# Sheet1.net
KiCad netlist of a schematic drawn in Altium Designer
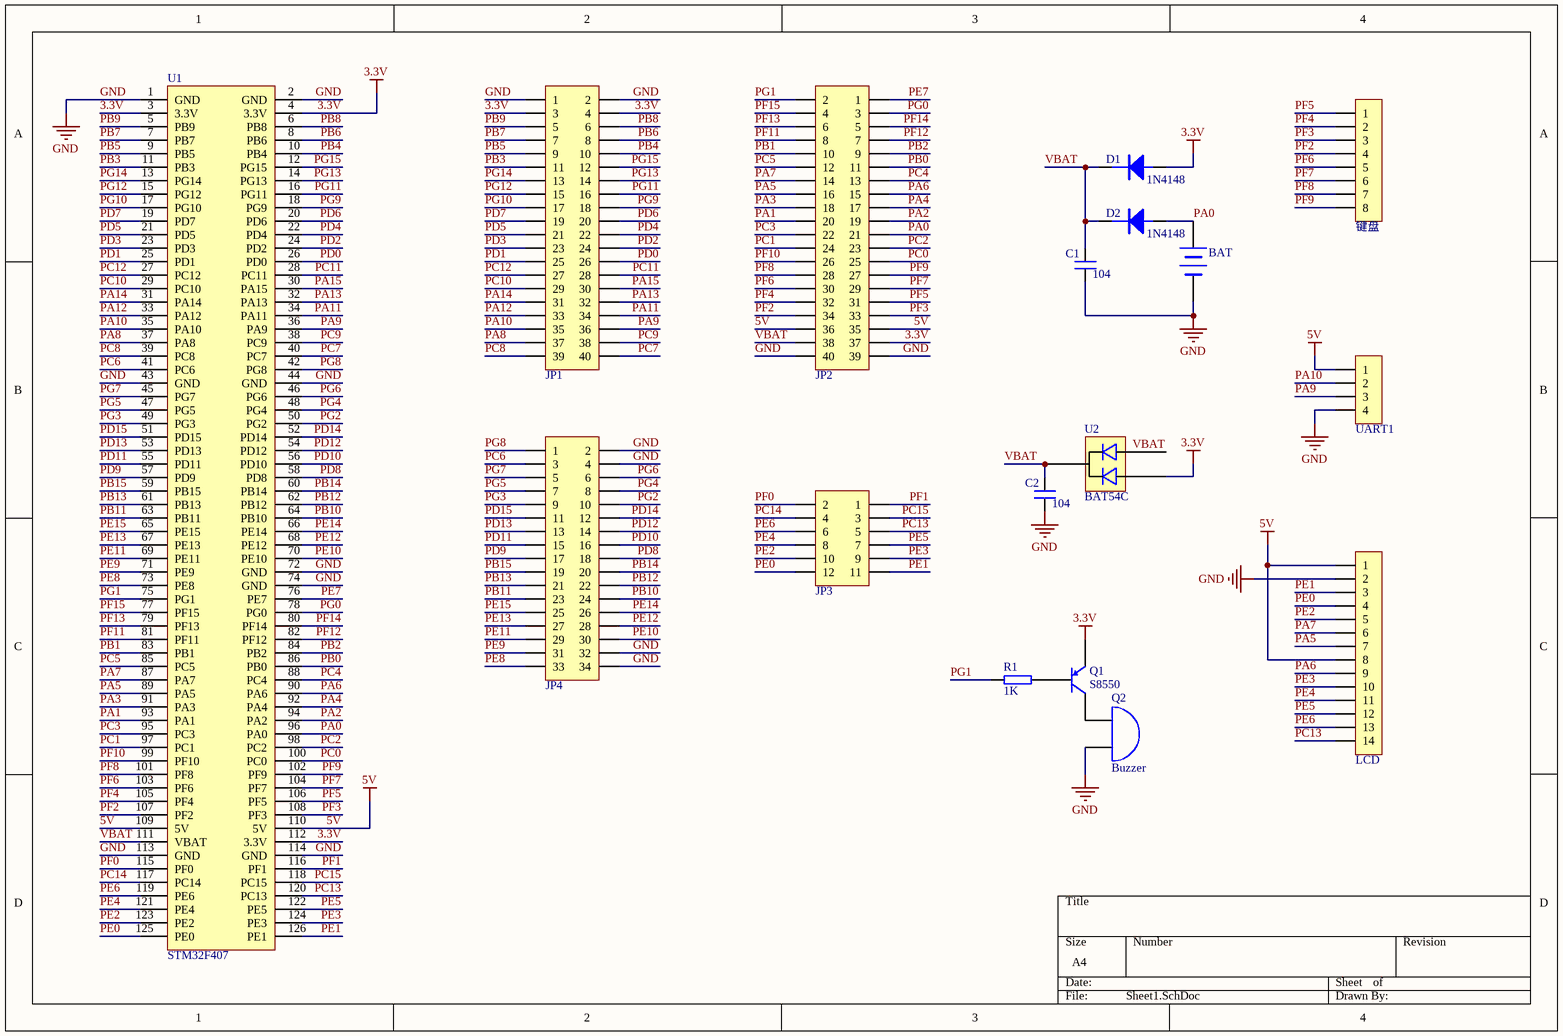
[diagram p0: Sheet1.SchDoc]

(export (version "E")
  (design (tool "Eeschema 10.0.6"))
  (components
    (comp (ref "BAT") (value "~") (footprint "BAT_SMD") (libsource (lib "Schlib1") (part "battery")))
    (comp (ref "C1")
      (value "104")
      (footprint "0805C")
      (description "电容")
      (fields (field (name "版权归属") "源创客"))
      (libsource (lib "Schlib1") (part "Capacitor"))
    )
    (comp (ref "C2")
      (value "104")
      (footprint "0805C")
      (description "电容")
      (fields (field (name "版权归属") "源创客"))
      (libsource (lib "Schlib1") (part "Capacitor"))
    )
    (comp (ref "D1") (value "1N4148") (footprint "SOD-123") (libsource (lib "Schlib1") (part "二极管")))
    (comp (ref "D2") (value "1N4148") (footprint "SOD-123") (libsource (lib "Schlib1") (part "二极管")))
    (comp (ref "JP1")
      (value "Header 2X11")
      (footprint "HDR-20X2")
      (description "20*2P接插件")
      (fields (field (name "版权归属") "源创客"))
      (libsource (lib "Schlib1") (part "Header 20X2u"))
    )
    (comp (ref "JP2")
      (value "Header 2X11")
      (footprint "HDR-20X2")
      (description "20*2P接插件")
      (fields (field (name "版权归属") "源创客"))
      (libsource (lib "") (part "Header 20X2u_1"))
    )
    (comp (ref "JP3")
      (value "Header 6X2")
      (footprint "HDR-6X2")
      (description "6*2P接插件")
      (fields (field (name "版权归属") "源创客"))
      (libsource (lib "Schlib1") (part "Header  6X2u"))
    )
    (comp (ref "JP4")
      (value "Header 2X11")
      (footprint "HDR-17X2")
      (description "17*2P接插件")
      (fields (field (name "版权归属") "源创客"))
      (libsource (lib "Schlib1") (part "Header 17X2u"))
    )
    (comp (ref "LCD")
      (value "HDR-1X14")
      (footprint "HDR-1X14_M")
      (description "14P接插件")
      (fields (field (name "版权归属") "源创客"))
      (libsource (lib "Schlib1") (part "Header 14u"))
    )
    (comp (ref "Q1") (value "S8550") (footprint "BAT54C/S8550") (libsource (lib "Schlib1") (part "S8550")))
    (comp (ref "Q2") (value "Buzzer") (footprint "7525蜂鸣器") (libsource (lib "Schlib1") (part "Buzzer")))
    (comp (ref "R1")
      (value "1K")
      (footprint "0805R")
      (description "电阻")
      (fields (field (name "版权归属") "源创客"))
      (libsource (lib "Schlib1") (part "Resistor"))
    )
    (comp (ref "U1")
      (value "STM32F407")
      (footprint "STM32F407ZGT6")
      (description "Header, 126-Pin, Dual row")
      (fields (field (name "PUBLISHER") "Altium Limited"))
      (libsource (lib "Schlib1") (part "STM32F407"))
    )
    (comp (ref "U2") (value "BAT54C") (footprint "BAT54C") (libsource (lib "Schlib1") (part "BAT54C")))
    (comp (ref "UART1")
      (value "HDR-1X4")
      (footprint "HDR-1X4")
      (description "4P接插件")
      (fields (field (name "版权归属") "源创客"))
      (libsource (lib "Schlib1") (part "Header 4u"))
    )
    (comp (ref "键盘")
      (value "HDR-1X8")
      (footprint "HDR-1X8_M")
      (description "8P接插件")
      (fields (field (name "版权归属") "源创客"))
      (libsource (lib "Schlib1") (part "Header 8u"))
    )
  )
  (nets
    (net (code "1") (name "/PA0") (class "Default")
      (node (ref "BAT") (pin "1") (pinfunction "+_1") (pintype "passive"))
      (node (ref "D2") (pin "1") (pinfunction "A_1") (pintype "passive"))
      (node (ref "JP2") (pin "21") (pinfunction "21_21") (pintype "passive"))
      (node (ref "U1") (pin "96") (pinfunction "PA0_96") (pintype "passive"))
    )
    (net (code "2") (name "/PA1") (class "Default")
      (node (ref "JP2") (pin "20") (pinfunction "20_20") (pintype "passive"))
      (node (ref "U1") (pin "93") (pinfunction "PA1_93") (pintype "passive"))
    )
    (net (code "3") (name "/PA2") (class "Default")
      (node (ref "JP2") (pin "19") (pinfunction "19_19") (pintype "passive"))
      (node (ref "U1") (pin "94") (pinfunction "PA2_94") (pintype "passive"))
    )
    (net (code "4") (name "/PA3") (class "Default")
      (node (ref "JP2") (pin "18") (pinfunction "18_18") (pintype "passive"))
      (node (ref "U1") (pin "91") (pinfunction "PA3_91") (pintype "passive"))
    )
    (net (code "5") (name "/PA4") (class "Default")
      (node (ref "JP2") (pin "17") (pinfunction "17_17") (pintype "passive"))
      (node (ref "U1") (pin "92") (pinfunction "PA4_92") (pintype "passive"))
    )
    (net (code "6") (name "/PA5") (class "Default")
      (node (ref "JP2") (pin "16") (pinfunction "16_16") (pintype "passive"))
      (node (ref "LCD") (pin "7") (pinfunction "7_7") (pintype "passive"))
      (node (ref "U1") (pin "89") (pinfunction "PA5_89") (pintype "passive"))
    )
    (net (code "7") (name "/PA6") (class "Default")
      (node (ref "JP2") (pin "15") (pinfunction "15_15") (pintype "passive"))
      (node (ref "LCD") (pin "9") (pinfunction "9_9") (pintype "passive"))
      (node (ref "U1") (pin "90") (pinfunction "PA6_90") (pintype "passive"))
    )
    (net (code "8") (name "/PA7") (class "Default")
      (node (ref "JP2") (pin "14") (pinfunction "14_14") (pintype "passive"))
      (node (ref "LCD") (pin "6") (pinfunction "6_6") (pintype "passive"))
      (node (ref "U1") (pin "87") (pinfunction "PA7_87") (pintype "passive"))
    )
    (net (code "9") (name "/PA8") (class "Default")
      (node (ref "JP1") (pin "37") (pinfunction "37_37") (pintype "passive"))
      (node (ref "U1") (pin "37") (pinfunction "PA8_37") (pintype "passive"))
    )
    (net (code "10") (name "/PA9") (class "Default")
      (node (ref "JP1") (pin "36") (pinfunction "36_36") (pintype "passive"))
      (node (ref "U1") (pin "36") (pinfunction "PA9_36") (pintype "passive"))
      (node (ref "UART1") (pin "3") (pinfunction "3_3") (pintype "passive"))
    )
    (net (code "11") (name "/PA10") (class "Default")
      (node (ref "JP1") (pin "35") (pinfunction "35_35") (pintype "passive"))
      (node (ref "U1") (pin "35") (pinfunction "PA10_35") (pintype "passive"))
      (node (ref "UART1") (pin "2") (pinfunction "2_2") (pintype "passive"))
    )
    (net (code "12") (name "/PA11") (class "Default")
      (node (ref "JP1") (pin "34") (pinfunction "34_34") (pintype "passive"))
      (node (ref "U1") (pin "34") (pinfunction "PA11_34") (pintype "passive"))
    )
    (net (code "13") (name "/PA12") (class "Default")
      (node (ref "JP1") (pin "33") (pinfunction "33_33") (pintype "passive"))
      (node (ref "U1") (pin "33") (pinfunction "PA12_33") (pintype "passive"))
    )
    (net (code "14") (name "/PA13") (class "Default")
      (node (ref "JP1") (pin "32") (pinfunction "32_32") (pintype "passive"))
      (node (ref "U1") (pin "32") (pinfunction "PA13_32") (pintype "passive"))
    )
    (net (code "15") (name "/PA14") (class "Default")
      (node (ref "JP1") (pin "31") (pinfunction "31_31") (pintype "passive"))
      (node (ref "U1") (pin "31") (pinfunction "PA14_31") (pintype "passive"))
    )
    (net (code "16") (name "/PA15") (class "Default")
      (node (ref "JP1") (pin "30") (pinfunction "30_30") (pintype "passive"))
      (node (ref "U1") (pin "30") (pinfunction "PA15_30") (pintype "passive"))
    )
    (net (code "17") (name "/PB0") (class "Default")
      (node (ref "JP2") (pin "11") (pinfunction "11_11") (pintype "passive"))
      (node (ref "U1") (pin "86") (pinfunction "PB0_86") (pintype "passive"))
    )
    (net (code "18") (name "/PB1") (class "Default")
      (node (ref "JP2") (pin "10") (pinfunction "10_10") (pintype "passive"))
      (node (ref "U1") (pin "83") (pinfunction "PB1_83") (pintype "passive"))
    )
    (net (code "19") (name "/PB2") (class "Default")
      (node (ref "JP2") (pin "9") (pinfunction "9_9") (pintype "passive"))
      (node (ref "U1") (pin "84") (pinfunction "PB2_84") (pintype "passive"))
    )
    (net (code "20") (name "/PB3") (class "Default")
      (node (ref "JP1") (pin "11") (pinfunction "11_11") (pintype "passive"))
      (node (ref "U1") (pin "11") (pinfunction "PB3_11") (pintype "passive"))
    )
    (net (code "21") (name "/PB4") (class "Default")
      (node (ref "JP1") (pin "10") (pinfunction "10_10") (pintype "passive"))
      (node (ref "U1") (pin "10") (pinfunction "PB4_10") (pintype "passive"))
    )
    (net (code "22") (name "/PB5") (class "Default")
      (node (ref "JP1") (pin "9") (pinfunction "9_9") (pintype "passive"))
      (node (ref "U1") (pin "9") (pinfunction "PB5_9") (pintype "passive"))
    )
    (net (code "23") (name "/PB6") (class "Default")
      (node (ref "JP1") (pin "8") (pinfunction "8_8") (pintype "passive"))
      (node (ref "U1") (pin "8") (pinfunction "PB6_8") (pintype "passive"))
    )
    (net (code "24") (name "/PB7") (class "Default")
      (node (ref "JP1") (pin "7") (pinfunction "7_7") (pintype "passive"))
      (node (ref "U1") (pin "7") (pinfunction "PB7_7") (pintype "passive"))
    )
    (net (code "25") (name "/PB8") (class "Default")
      (node (ref "JP1") (pin "6") (pinfunction "6_6") (pintype "passive"))
      (node (ref "U1") (pin "6") (pinfunction "PB8_6") (pintype "passive"))
    )
    (net (code "26") (name "/PB9") (class "Default")
      (node (ref "JP1") (pin "5") (pinfunction "5_5") (pintype "passive"))
      (node (ref "U1") (pin "5") (pinfunction "PB9_5") (pintype "passive"))
    )
    (net (code "27") (name "/PB10") (class "Default")
      (node (ref "JP4") (pin "24") (pinfunction "24_24") (pintype "passive"))
      (node (ref "U1") (pin "64") (pinfunction "PB10_64") (pintype "passive"))
    )
    (net (code "28") (name "/PB11") (class "Default")
      (node (ref "JP4") (pin "23") (pinfunction "23_23") (pintype "passive"))
      (node (ref "U1") (pin "63") (pinfunction "PB11_63") (pintype "passive"))
    )
    (net (code "29") (name "/PB12") (class "Default")
      (node (ref "JP4") (pin "22") (pinfunction "22_22") (pintype "passive"))
      (node (ref "U1") (pin "62") (pinfunction "PB12_62") (pintype "passive"))
    )
    (net (code "30") (name "/PB13") (class "Default")
      (node (ref "JP4") (pin "21") (pinfunction "21_21") (pintype "passive"))
      (node (ref "U1") (pin "61") (pinfunction "PB13_61") (pintype "passive"))
    )
    (net (code "31") (name "/PB14") (class "Default")
      (node (ref "JP4") (pin "20") (pinfunction "20_20") (pintype "passive"))
      (node (ref "U1") (pin "60") (pinfunction "PB14_60") (pintype "passive"))
    )
    (net (code "32") (name "/PB15") (class "Default")
      (node (ref "JP4") (pin "19") (pinfunction "19_19") (pintype "passive"))
      (node (ref "U1") (pin "59") (pinfunction "PB15_59") (pintype "passive"))
    )
    (net (code "33") (name "/PC0") (class "Default")
      (node (ref "JP2") (pin "25") (pinfunction "25_25") (pintype "passive"))
      (node (ref "U1") (pin "100") (pinfunction "PC0_100") (pintype "passive"))
    )
    (net (code "34") (name "/PC1") (class "Default")
      (node (ref "JP2") (pin "24") (pinfunction "24_24") (pintype "passive"))
      (node (ref "U1") (pin "97") (pinfunction "PC1_97") (pintype "passive"))
    )
    (net (code "35") (name "/PC2") (class "Default")
      (node (ref "JP2") (pin "23") (pinfunction "23_23") (pintype "passive"))
      (node (ref "U1") (pin "98") (pinfunction "PC2_98") (pintype "passive"))
    )
    (net (code "36") (name "/PC3") (class "Default")
      (node (ref "JP2") (pin "22") (pinfunction "22_22") (pintype "passive"))
      (node (ref "U1") (pin "95") (pinfunction "PC3_95") (pintype "passive"))
    )
    (net (code "37") (name "/PC4") (class "Default")
      (node (ref "JP2") (pin "13") (pinfunction "13_13") (pintype "passive"))
      (node (ref "U1") (pin "88") (pinfunction "PC4_88") (pintype "passive"))
    )
    (net (code "38") (name "/PC5") (class "Default")
      (node (ref "JP2") (pin "12") (pinfunction "12_12") (pintype "passive"))
      (node (ref "U1") (pin "85") (pinfunction "PC5_85") (pintype "passive"))
    )
    (net (code "39") (name "/PC6") (class "Default")
      (node (ref "JP4") (pin "3") (pinfunction "3_3") (pintype "passive"))
      (node (ref "U1") (pin "41") (pinfunction "PC6_41") (pintype "passive"))
    )
    (net (code "40") (name "/PC7") (class "Default")
      (node (ref "JP1") (pin "40") (pinfunction "40_40") (pintype "passive"))
      (node (ref "U1") (pin "40") (pinfunction "PC7_40") (pintype "passive"))
    )
    (net (code "41") (name "/PC8") (class "Default")
      (node (ref "JP1") (pin "39") (pinfunction "39_39") (pintype "passive"))
      (node (ref "U1") (pin "39") (pinfunction "PC8_39") (pintype "passive"))
    )
    (net (code "42") (name "/PC9") (class "Default")
      (node (ref "JP1") (pin "38") (pinfunction "38_38") (pintype "passive"))
      (node (ref "U1") (pin "38") (pinfunction "PC9_38") (pintype "passive"))
    )
    (net (code "43") (name "/PC10") (class "Default")
      (node (ref "JP1") (pin "29") (pinfunction "29_29") (pintype "passive"))
      (node (ref "U1") (pin "29") (pinfunction "PC10_29") (pintype "passive"))
    )
    (net (code "44") (name "/PC11") (class "Default")
      (node (ref "JP1") (pin "28") (pinfunction "28_28") (pintype "passive"))
      (node (ref "U1") (pin "28") (pinfunction "PC11_28") (pintype "passive"))
    )
    (net (code "45") (name "/PC12") (class "Default")
      (node (ref "JP1") (pin "27") (pinfunction "27_27") (pintype "passive"))
      (node (ref "U1") (pin "27") (pinfunction "PC12_27") (pintype "passive"))
    )
    (net (code "46") (name "/PC13") (class "Default")
      (node (ref "JP3") (pin "5") (pinfunction "5_5") (pintype "passive"))
      (node (ref "LCD") (pin "14") (pinfunction "14_14") (pintype "passive"))
      (node (ref "U1") (pin "120") (pinfunction "PC13_120") (pintype "passive"))
    )
    (net (code "47") (name "/PC14") (class "Default")
      (node (ref "JP3") (pin "4") (pinfunction "4_4") (pintype "passive"))
      (node (ref "U1") (pin "117") (pinfunction "PC14_117") (pintype "passive"))
    )
    (net (code "48") (name "/PC15") (class "Default")
      (node (ref "JP3") (pin "3") (pinfunction "3_3") (pintype "passive"))
      (node (ref "U1") (pin "118") (pinfunction "PC15_118") (pintype "passive"))
    )
    (net (code "49") (name "/PD0") (class "Default")
      (node (ref "JP1") (pin "26") (pinfunction "26_26") (pintype "passive"))
      (node (ref "U1") (pin "26") (pinfunction "PD0_26") (pintype "passive"))
    )
    (net (code "50") (name "/PD1") (class "Default")
      (node (ref "JP1") (pin "25") (pinfunction "25_25") (pintype "passive"))
      (node (ref "U1") (pin "25") (pinfunction "PD1_25") (pintype "passive"))
    )
    (net (code "51") (name "/PD2") (class "Default")
      (node (ref "JP1") (pin "24") (pinfunction "24_24") (pintype "passive"))
      (node (ref "U1") (pin "24") (pinfunction "PD2_24") (pintype "passive"))
    )
    (net (code "52") (name "/PD3") (class "Default")
      (node (ref "JP1") (pin "23") (pinfunction "23_23") (pintype "passive"))
      (node (ref "U1") (pin "23") (pinfunction "PD3_23") (pintype "passive"))
    )
    (net (code "53") (name "/PD4") (class "Default")
      (node (ref "JP1") (pin "22") (pinfunction "22_22") (pintype "passive"))
      (node (ref "U1") (pin "22") (pinfunction "PD4_22") (pintype "passive"))
    )
    (net (code "54") (name "/PD5") (class "Default")
      (node (ref "JP1") (pin "21") (pinfunction "21_21") (pintype "passive"))
      (node (ref "U1") (pin "21") (pinfunction "PD5_21") (pintype "passive"))
    )
    (net (code "55") (name "/PD6") (class "Default")
      (node (ref "JP1") (pin "20") (pinfunction "20_20") (pintype "passive"))
      (node (ref "U1") (pin "20") (pinfunction "PD6_20") (pintype "passive"))
    )
    (net (code "56") (name "/PD7") (class "Default")
      (node (ref "JP1") (pin "19") (pinfunction "19_19") (pintype "passive"))
      (node (ref "U1") (pin "19") (pinfunction "PD7_19") (pintype "passive"))
    )
    (net (code "57") (name "/PD8") (class "Default")
      (node (ref "JP4") (pin "18") (pinfunction "18_18") (pintype "passive"))
      (node (ref "U1") (pin "58") (pinfunction "PD8_58") (pintype "passive"))
    )
    (net (code "58") (name "/PD9") (class "Default")
      (node (ref "JP4") (pin "17") (pinfunction "17_17") (pintype "passive"))
      (node (ref "U1") (pin "57") (pinfunction "PD9_57") (pintype "passive"))
    )
    (net (code "59") (name "/PD10") (class "Default")
      (node (ref "JP4") (pin "16") (pinfunction "16_16") (pintype "passive"))
      (node (ref "U1") (pin "56") (pinfunction "PD10_56") (pintype "passive"))
    )
    (net (code "60") (name "/PD11") (class "Default")
      (node (ref "JP4") (pin "15") (pinfunction "15_15") (pintype "passive"))
      (node (ref "U1") (pin "55") (pinfunction "PD11_55") (pintype "passive"))
    )
    (net (code "61") (name "/PD12") (class "Default")
      (node (ref "JP4") (pin "14") (pinfunction "14_14") (pintype "passive"))
      (node (ref "U1") (pin "54") (pinfunction "PD12_54") (pintype "passive"))
    )
    (net (code "62") (name "/PD13") (class "Default")
      (node (ref "JP4") (pin "13") (pinfunction "13_13") (pintype "passive"))
      (node (ref "U1") (pin "53") (pinfunction "PD13_53") (pintype "passive"))
    )
    (net (code "63") (name "/PD14") (class "Default")
      (node (ref "JP4") (pin "12") (pinfunction "12_12") (pintype "passive"))
      (node (ref "U1") (pin "52") (pinfunction "PD14_52") (pintype "passive"))
    )
    (net (code "64") (name "/PD15") (class "Default")
      (node (ref "JP4") (pin "11") (pinfunction "11_11") (pintype "passive"))
      (node (ref "U1") (pin "51") (pinfunction "PD15_51") (pintype "passive"))
    )
    (net (code "65") (name "/PE0") (class "Default")
      (node (ref "JP3") (pin "12") (pinfunction "12_12") (pintype "passive"))
      (node (ref "LCD") (pin "4") (pinfunction "4_4") (pintype "passive"))
      (node (ref "U1") (pin "125") (pinfunction "PE0_125") (pintype "passive"))
    )
    (net (code "66") (name "/PE1") (class "Default")
      (node (ref "JP3") (pin "11") (pinfunction "11_11") (pintype "passive"))
      (node (ref "LCD") (pin "3") (pinfunction "3_3") (pintype "passive"))
      (node (ref "U1") (pin "126") (pinfunction "PE1_126") (pintype "passive"))
    )
    (net (code "67") (name "/PE2") (class "Default")
      (node (ref "JP3") (pin "10") (pinfunction "10_10") (pintype "passive"))
      (node (ref "LCD") (pin "5") (pinfunction "5_5") (pintype "passive"))
      (node (ref "U1") (pin "123") (pinfunction "PE2_123") (pintype "passive"))
    )
    (net (code "68") (name "/PE3") (class "Default")
      (node (ref "JP3") (pin "9") (pinfunction "9_9") (pintype "passive"))
      (node (ref "LCD") (pin "10") (pinfunction "10_10") (pintype "passive"))
      (node (ref "U1") (pin "124") (pinfunction "PE3_124") (pintype "passive"))
    )
    (net (code "69") (name "/PE4") (class "Default")
      (node (ref "JP3") (pin "8") (pinfunction "8_8") (pintype "passive"))
      (node (ref "LCD") (pin "11") (pinfunction "11_11") (pintype "passive"))
      (node (ref "U1") (pin "121") (pinfunction "PE4_121") (pintype "passive"))
    )
    (net (code "70") (name "/PE5") (class "Default")
      (node (ref "JP3") (pin "7") (pinfunction "7_7") (pintype "passive"))
      (node (ref "LCD") (pin "12") (pinfunction "12_12") (pintype "passive"))
      (node (ref "U1") (pin "122") (pinfunction "PE5_122") (pintype "passive"))
    )
    (net (code "71") (name "/PE6") (class "Default")
      (node (ref "JP3") (pin "6") (pinfunction "6_6") (pintype "passive"))
      (node (ref "LCD") (pin "13") (pinfunction "13_13") (pintype "passive"))
      (node (ref "U1") (pin "119") (pinfunction "PE6_119") (pintype "passive"))
    )
    (net (code "72") (name "/PE7") (class "Default")
      (node (ref "JP2") (pin "1") (pinfunction "1_1") (pintype "passive"))
      (node (ref "U1") (pin "76") (pinfunction "PE7_76") (pintype "passive"))
    )
    (net (code "73") (name "/PE8") (class "Default")
      (node (ref "JP4") (pin "33") (pinfunction "33_33") (pintype "passive"))
      (node (ref "U1") (pin "73") (pinfunction "PE8_73") (pintype "passive"))
    )
    (net (code "74") (name "/PE9") (class "Default")
      (node (ref "JP4") (pin "31") (pinfunction "31_31") (pintype "passive"))
      (node (ref "U1") (pin "71") (pinfunction "PE9_71") (pintype "passive"))
    )
    (net (code "75") (name "/PE10") (class "Default")
      (node (ref "JP4") (pin "30") (pinfunction "30_30") (pintype "passive"))
      (node (ref "U1") (pin "70") (pinfunction "PE10_70") (pintype "passive"))
    )
    (net (code "76") (name "/PE11") (class "Default")
      (node (ref "JP4") (pin "29") (pinfunction "29_29") (pintype "passive"))
      (node (ref "U1") (pin "69") (pinfunction "PE11_69") (pintype "passive"))
    )
    (net (code "77") (name "/PE12") (class "Default")
      (node (ref "JP4") (pin "28") (pinfunction "28_28") (pintype "passive"))
      (node (ref "U1") (pin "68") (pinfunction "PE12_68") (pintype "passive"))
    )
    (net (code "78") (name "/PE13") (class "Default")
      (node (ref "JP4") (pin "27") (pinfunction "27_27") (pintype "passive"))
      (node (ref "U1") (pin "67") (pinfunction "PE13_67") (pintype "passive"))
    )
    (net (code "79") (name "/PE14") (class "Default")
      (node (ref "JP4") (pin "26") (pinfunction "26_26") (pintype "passive"))
      (node (ref "U1") (pin "66") (pinfunction "PE14_66") (pintype "passive"))
    )
    (net (code "80") (name "/PE15") (class "Default")
      (node (ref "JP4") (pin "25") (pinfunction "25_25") (pintype "passive"))
      (node (ref "U1") (pin "65") (pinfunction "PE15_65") (pintype "passive"))
    )
    (net (code "81") (name "/PF0") (class "Default")
      (node (ref "JP3") (pin "2") (pinfunction "2_2") (pintype "passive"))
      (node (ref "U1") (pin "115") (pinfunction "PF0_115") (pintype "passive"))
    )
    (net (code "82") (name "/PF1") (class "Default")
      (node (ref "JP3") (pin "1") (pinfunction "1_1") (pintype "passive"))
      (node (ref "U1") (pin "116") (pinfunction "PF1_116") (pintype "passive"))
    )
    (net (code "83") (name "/PF2") (class "Default")
      (node (ref "JP2") (pin "34") (pinfunction "34_34") (pintype "passive"))
      (node (ref "U1") (pin "107") (pinfunction "PF2_107") (pintype "passive"))
      (node (ref "键盘") (pin "4") (pinfunction "4_4") (pintype "passive"))
    )
    (net (code "84") (name "/PF3") (class "Default")
      (node (ref "JP2") (pin "33") (pinfunction "33_33") (pintype "passive"))
      (node (ref "U1") (pin "108") (pinfunction "PF3_108") (pintype "passive"))
      (node (ref "键盘") (pin "3") (pinfunction "3_3") (pintype "passive"))
    )
    (net (code "85") (name "/PF4") (class "Default")
      (node (ref "JP2") (pin "32") (pinfunction "32_32") (pintype "passive"))
      (node (ref "U1") (pin "105") (pinfunction "PF4_105") (pintype "passive"))
      (node (ref "键盘") (pin "2") (pinfunction "2_2") (pintype "passive"))
    )
    (net (code "86") (name "/PF5") (class "Default")
      (node (ref "JP2") (pin "31") (pinfunction "31_31") (pintype "passive"))
      (node (ref "U1") (pin "106") (pinfunction "PF5_106") (pintype "passive"))
      (node (ref "键盘") (pin "1") (pinfunction "1_1") (pintype "passive"))
    )
    (net (code "87") (name "/PF6") (class "Default")
      (node (ref "JP2") (pin "30") (pinfunction "30_30") (pintype "passive"))
      (node (ref "U1") (pin "103") (pinfunction "PF6_103") (pintype "passive"))
      (node (ref "键盘") (pin "5") (pinfunction "5_5") (pintype "passive"))
    )
    (net (code "88") (name "/PF7") (class "Default")
      (node (ref "JP2") (pin "29") (pinfunction "29_29") (pintype "passive"))
      (node (ref "U1") (pin "104") (pinfunction "PF7_104") (pintype "passive"))
      (node (ref "键盘") (pin "6") (pinfunction "6_6") (pintype "passive"))
    )
    (net (code "89") (name "/PF8") (class "Default")
      (node (ref "JP2") (pin "28") (pinfunction "28_28") (pintype "passive"))
      (node (ref "U1") (pin "101") (pinfunction "PF8_101") (pintype "passive"))
      (node (ref "键盘") (pin "7") (pinfunction "7_7") (pintype "passive"))
    )
    (net (code "90") (name "/PF9") (class "Default")
      (node (ref "JP2") (pin "27") (pinfunction "27_27") (pintype "passive"))
      (node (ref "U1") (pin "102") (pinfunction "PF9_102") (pintype "passive"))
      (node (ref "键盘") (pin "8") (pinfunction "8_8") (pintype "passive"))
    )
    (net (code "91") (name "/PF10") (class "Default")
      (node (ref "JP2") (pin "26") (pinfunction "26_26") (pintype "passive"))
      (node (ref "U1") (pin "99") (pinfunction "PF10_99") (pintype "passive"))
    )
    (net (code "92") (name "/PF11") (class "Default")
      (node (ref "JP2") (pin "8") (pinfunction "8_8") (pintype "passive"))
      (node (ref "U1") (pin "81") (pinfunction "PF11_81") (pintype "passive"))
    )
    (net (code "93") (name "/PF12") (class "Default")
      (node (ref "JP2") (pin "7") (pinfunction "7_7") (pintype "passive"))
      (node (ref "U1") (pin "82") (pinfunction "PF12_82") (pintype "passive"))
    )
    (net (code "94") (name "/PF13") (class "Default")
      (node (ref "JP2") (pin "6") (pinfunction "6_6") (pintype "passive"))
      (node (ref "U1") (pin "79") (pinfunction "PF13_79") (pintype "passive"))
    )
    (net (code "95") (name "/PF14") (class "Default")
      (node (ref "JP2") (pin "5") (pinfunction "5_5") (pintype "passive"))
      (node (ref "U1") (pin "80") (pinfunction "PF14_80") (pintype "passive"))
    )
    (net (code "96") (name "/PF15") (class "Default")
      (node (ref "JP2") (pin "4") (pinfunction "4_4") (pintype "passive"))
      (node (ref "U1") (pin "77") (pinfunction "PF15_77") (pintype "passive"))
    )
    (net (code "97") (name "/PG0") (class "Default")
      (node (ref "JP2") (pin "3") (pinfunction "3_3") (pintype "passive"))
      (node (ref "U1") (pin "78") (pinfunction "PG0_78") (pintype "passive"))
    )
    (net (code "98") (name "/PG1") (class "Default")
      (node (ref "JP2") (pin "2") (pinfunction "2_2") (pintype "passive"))
      (node (ref "R1") (pin "1") (pinfunction "1_1") (pintype "passive"))
      (node (ref "U1") (pin "75") (pinfunction "PG1_75") (pintype "passive"))
    )
    (net (code "99") (name "/PG2") (class "Default")
      (node (ref "JP4") (pin "10") (pinfunction "10_10") (pintype "passive"))
      (node (ref "U1") (pin "50") (pinfunction "PG2_50") (pintype "passive"))
    )
    (net (code "100") (name "/PG3") (class "Default")
      (node (ref "JP4") (pin "9") (pinfunction "9_9") (pintype "passive"))
      (node (ref "U1") (pin "49") (pinfunction "PG3_49") (pintype "passive"))
    )
    (net (code "101") (name "/PG4") (class "Default")
      (node (ref "JP4") (pin "8") (pinfunction "8_8") (pintype "passive"))
      (node (ref "U1") (pin "48") (pinfunction "PG4_48") (pintype "passive"))
    )
    (net (code "102") (name "/PG5") (class "Default")
      (node (ref "JP4") (pin "7") (pinfunction "7_7") (pintype "passive"))
      (node (ref "U1") (pin "47") (pinfunction "PG5_47") (pintype "passive"))
    )
    (net (code "103") (name "/PG6") (class "Default")
      (node (ref "JP4") (pin "6") (pinfunction "6_6") (pintype "passive"))
      (node (ref "U1") (pin "46") (pinfunction "PG6_46") (pintype "passive"))
    )
    (net (code "104") (name "/PG7") (class "Default")
      (node (ref "JP4") (pin "5") (pinfunction "5_5") (pintype "passive"))
      (node (ref "U1") (pin "45") (pinfunction "PG7_45") (pintype "passive"))
    )
    (net (code "105") (name "/PG8") (class "Default")
      (node (ref "JP4") (pin "1") (pinfunction "1_1") (pintype "passive"))
      (node (ref "U1") (pin "42") (pinfunction "PG8_42") (pintype "passive"))
    )
    (net (code "106") (name "/PG9") (class "Default")
      (node (ref "JP1") (pin "18") (pinfunction "18_18") (pintype "passive"))
      (node (ref "U1") (pin "18") (pinfunction "PG9_18") (pintype "passive"))
    )
    (net (code "107") (name "/PG10") (class "Default")
      (node (ref "JP1") (pin "17") (pinfunction "17_17") (pintype "passive"))
      (node (ref "U1") (pin "17") (pinfunction "PG10_17") (pintype "passive"))
    )
    (net (code "108") (name "/PG11") (class "Default")
      (node (ref "JP1") (pin "16") (pinfunction "16_16") (pintype "passive"))
      (node (ref "U1") (pin "16") (pinfunction "PG11_16") (pintype "passive"))
    )
    (net (code "109") (name "/PG12") (class "Default")
      (node (ref "JP1") (pin "15") (pinfunction "15_15") (pintype "passive"))
      (node (ref "U1") (pin "15") (pinfunction "PG12_15") (pintype "passive"))
    )
    (net (code "110") (name "/PG13") (class "Default")
      (node (ref "JP1") (pin "14") (pinfunction "14_14") (pintype "passive"))
      (node (ref "U1") (pin "14") (pinfunction "PG13_14") (pintype "passive"))
    )
    (net (code "111") (name "/PG14") (class "Default")
      (node (ref "JP1") (pin "13") (pinfunction "13_13") (pintype "passive"))
      (node (ref "U1") (pin "13") (pinfunction "PG14_13") (pintype "passive"))
    )
    (net (code "112") (name "/PG15") (class "Default")
      (node (ref "JP1") (pin "12") (pinfunction "12_12") (pintype "passive"))
      (node (ref "U1") (pin "12") (pinfunction "PG15_12") (pintype "passive"))
    )
    (net (code "113") (name "/VBAT") (class "Default")
      (node (ref "C1") (pin "2") (pinfunction "2_2") (pintype "passive"))
      (node (ref "C2") (pin "1") (pinfunction "1_1") (pintype "passive"))
      (node (ref "D1") (pin "2") (pinfunction "K_2") (pintype "passive"))
      (node (ref "D2") (pin "2") (pinfunction "K_2") (pintype "passive"))
      (node (ref "JP2") (pin "38") (pinfunction "38_38") (pintype "passive"))
      (node (ref "U1") (pin "111") (pinfunction "VBAT_111") (pintype "passive"))
      (node (ref "U2") (pin "1") (pinfunction "*_1") (pintype "passive"))
      (node (ref "U2") (pin "3") (pinfunction "*_3") (pintype "passive"))
    )
    (net (code "114") (name "3.3V") (class "Default")
      (node (ref "D1") (pin "1") (pinfunction "A_1") (pintype "passive"))
      (node (ref "JP1") (pin "3") (pinfunction "3_3") (pintype "passive"))
      (node (ref "JP1") (pin "4") (pinfunction "4_4") (pintype "passive"))
      (node (ref "JP2") (pin "37") (pinfunction "37_37") (pintype "passive"))
      (node (ref "Q1") (pin "1") (pinfunction "E_1") (pintype "passive"))
      (node (ref "U1") (pin "112") (pinfunction "3.3V_112") (pintype "passive"))
      (node (ref "U1") (pin "3") (pinfunction "3.3V_3") (pintype "passive"))
      (node (ref "U1") (pin "4") (pinfunction "3.3V_4") (pintype "passive"))
      (node (ref "U2") (pin "2") (pinfunction "*_2") (pintype "passive"))
    )
    (net (code "115") (name "5V") (class "Default")
      (node (ref "JP2") (pin "35") (pinfunction "35_35") (pintype "passive"))
      (node (ref "JP2") (pin "36") (pinfunction "36_36") (pintype "passive"))
      (node (ref "LCD") (pin "1") (pinfunction "1_1") (pintype "passive"))
      (node (ref "LCD") (pin "8") (pinfunction "8_8") (pintype "passive"))
      (node (ref "U1") (pin "109") (pinfunction "5V_109") (pintype "passive"))
      (node (ref "U1") (pin "110") (pinfunction "5V_110") (pintype "passive"))
      (node (ref "UART1") (pin "1") (pinfunction "1_1") (pintype "passive"))
    )
    (net (code "116") (name "GND") (class "Default")
      (node (ref "BAT") (pin "2") (pinfunction "-_2") (pintype "passive"))
      (node (ref "C1") (pin "1") (pinfunction "1_1") (pintype "passive"))
      (node (ref "C2") (pin "2") (pinfunction "2_2") (pintype "passive"))
      (node (ref "JP1") (pin "1") (pinfunction "1_1") (pintype "passive"))
      (node (ref "JP1") (pin "2") (pinfunction "2_2") (pintype "passive"))
      (node (ref "JP2") (pin "39") (pinfunction "39_39") (pintype "passive"))
      (node (ref "JP2") (pin "40") (pinfunction "40_40") (pintype "passive"))
      (node (ref "JP4") (pin "2") (pinfunction "2_2") (pintype "passive"))
      (node (ref "JP4") (pin "32") (pinfunction "32_32") (pintype "passive"))
      (node (ref "JP4") (pin "34") (pinfunction "34_34") (pintype "passive"))
      (node (ref "JP4") (pin "4") (pinfunction "4_4") (pintype "passive"))
      (node (ref "LCD") (pin "2") (pinfunction "2_2") (pintype "passive"))
      (node (ref "Q2") (pin "2") (pinfunction "2_2") (pintype "passive"))
      (node (ref "U1") (pin "1") (pinfunction "GND_1") (pintype "passive"))
      (node (ref "U1") (pin "113") (pinfunction "GND_113") (pintype "passive"))
      (node (ref "U1") (pin "114") (pinfunction "GND_114") (pintype "passive"))
      (node (ref "U1") (pin "2") (pinfunction "GND_2") (pintype "passive"))
      (node (ref "U1") (pin "43") (pinfunction "GND_43") (pintype "passive"))
      (node (ref "U1") (pin "44") (pinfunction "GND_44") (pintype "passive"))
      (node (ref "U1") (pin "72") (pinfunction "GND_72") (pintype "passive"))
      (node (ref "U1") (pin "74") (pinfunction "GND_74") (pintype "passive"))
      (node (ref "UART1") (pin "4") (pinfunction "4_4") (pintype "passive"))
    )
    (net (code "117") (name "Net-(Q1-B)") (class "Default")
      (node (ref "Q1") (pin "2") (pinfunction "B_2") (pintype "passive"))
      (node (ref "R1") (pin "2") (pinfunction "2_2") (pintype "passive"))
    )
    (net (code "118") (name "Net-(Q1-C)") (class "Default")
      (node (ref "Q1") (pin "3") (pinfunction "C_3") (pintype "passive"))
      (node (ref "Q2") (pin "1") (pinfunction "1_1") (pintype "passive"))
    )
  )
)
